# InterfaceV1_2.net
KiCad netlist of a schematic drawn in Altium Designer
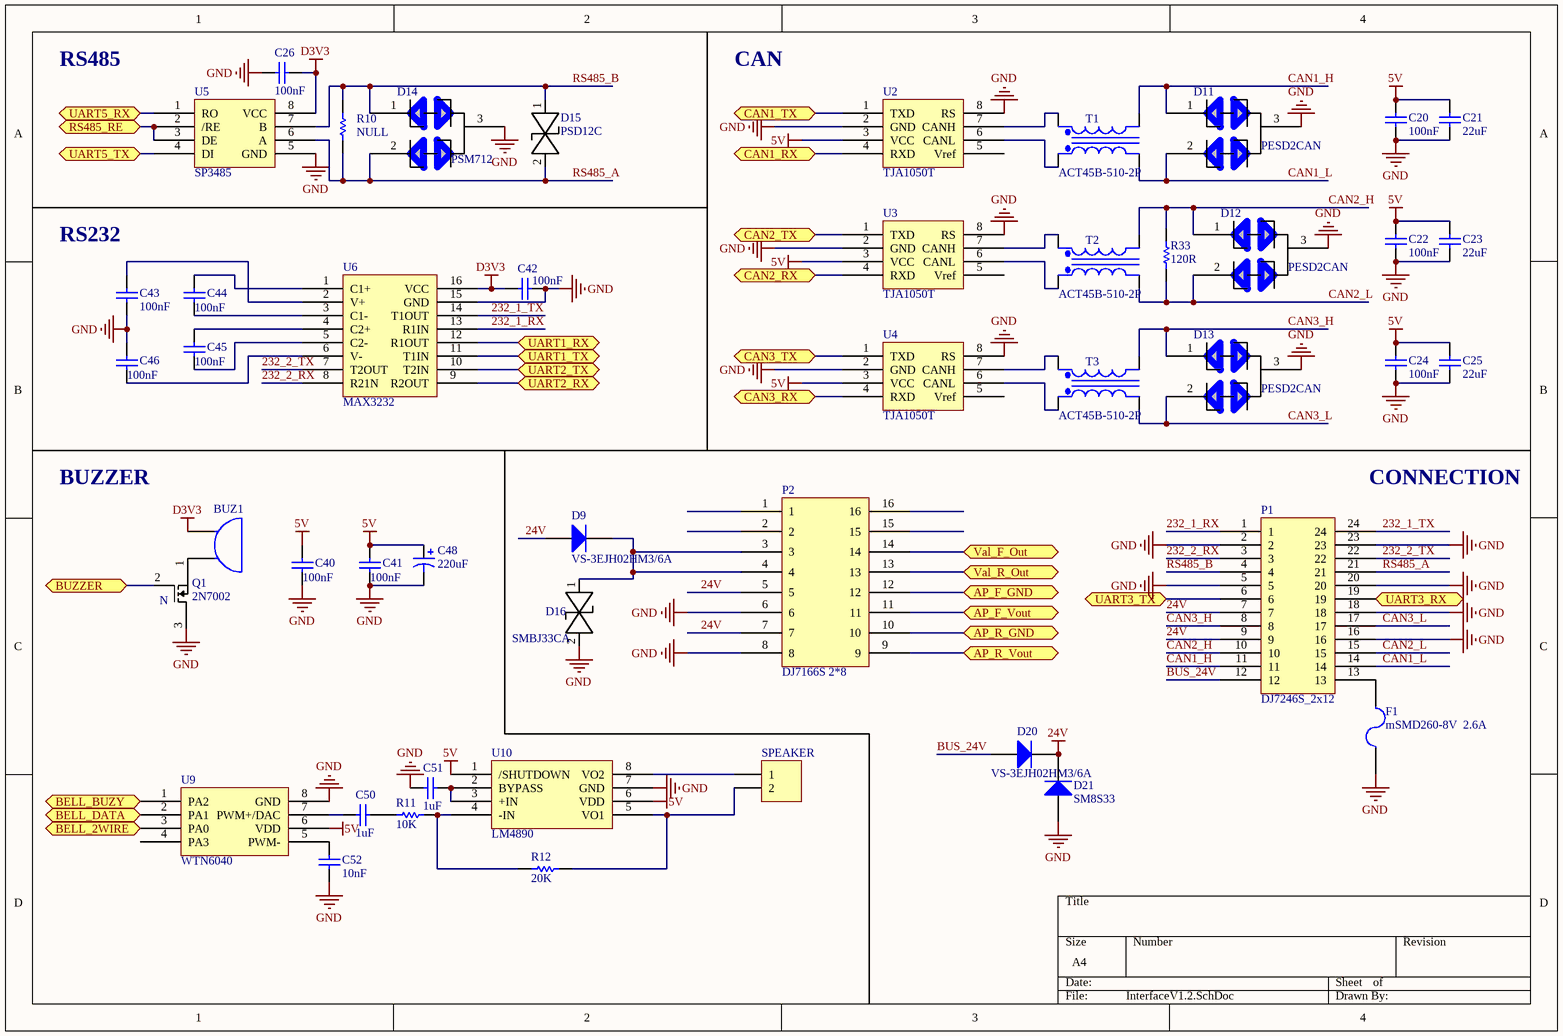
[diagram p0: InterfaceV1.2.SchDoc]

(export (version "E")
  (design (tool "Eeschema 10.0.6"))
  (components
    (comp (ref "BUZ1")
      (value "BUZZER")
      (footprint "BUZ0905")
      (description "Buzzer")
      (libsource (lib "杂元件库") (part "BUZZER"))
    )
    (comp (ref "C20")
      (value "100nF")
      (footprint "BinFeng:0402")
      (description "Capacitor")
      (fields (field (name "PUBLISHER") "Altium Limited"))
      (libsource (lib "Miscellaneous Devices") (part "Cap"))
    )
    (comp (ref "C21")
      (value "22uF")
      (footprint "0805")
      (description "Capacitor")
      (fields (field (name "PUBLISHER") "Altium Limited"))
      (libsource (lib "Miscellaneous Devices") (part "Cap"))
    )
    (comp (ref "C22")
      (value "100nF")
      (footprint "BinFeng:0402")
      (description "Capacitor")
      (fields (field (name "PUBLISHER") "Altium Limited"))
      (libsource (lib "Miscellaneous Devices") (part "Cap"))
    )
    (comp (ref "C23")
      (value "22uF")
      (footprint "0805")
      (description "Capacitor")
      (fields (field (name "PUBLISHER") "Altium Limited"))
      (libsource (lib "Miscellaneous Devices") (part "Cap"))
    )
    (comp (ref "C24")
      (value "100nF")
      (footprint "BinFeng:0402")
      (description "Capacitor")
      (fields (field (name "PUBLISHER") "Altium Limited"))
      (libsource (lib "Miscellaneous Devices") (part "Cap"))
    )
    (comp (ref "C25")
      (value "22uF")
      (footprint "0805")
      (description "Capacitor")
      (fields (field (name "PUBLISHER") "Altium Limited"))
      (libsource (lib "Miscellaneous Devices") (part "Cap"))
    )
    (comp (ref "C26")
      (value "100nF")
      (footprint "BinFeng:0603")
      (description "Capacitor")
      (fields (field (name "PUBLISHER") "Altium Limited"))
      (libsource (lib "Miscellaneous Devices") (part "Cap"))
    )
    (comp (ref "C40")
      (value "100nF")
      (footprint "BinFeng:0402")
      (description "Capacitor")
      (fields (field (name "PUBLISHER") "Altium Limited"))
      (libsource (lib "Miscellaneous Devices") (part "Cap"))
    )
    (comp (ref "C41")
      (value "100nF")
      (footprint "BinFeng:0402")
      (description "Capacitor")
      (fields (field (name "PUBLISHER") "Altium Limited"))
      (libsource (lib "Miscellaneous Devices") (part "Cap"))
    )
    (comp (ref "C42")
      (value "100nF")
      (footprint "BinFeng:0402")
      (description "Capacitor")
      (fields (field (name "PUBLISHER") "Altium Limited"))
      (libsource (lib "Miscellaneous Devices") (part "Cap"))
    )
    (comp (ref "C43")
      (value "100nF")
      (footprint "BinFeng:0402")
      (description "Capacitor")
      (fields (field (name "PUBLISHER") "Altium Limited"))
      (libsource (lib "Miscellaneous Devices") (part "Cap"))
    )
    (comp (ref "C44")
      (value "100nF")
      (footprint "BinFeng:0402")
      (description "Capacitor")
      (fields (field (name "PUBLISHER") "Altium Limited"))
      (libsource (lib "Miscellaneous Devices") (part "Cap"))
    )
    (comp (ref "C45")
      (value "100nF")
      (footprint "BinFeng:0402")
      (description "Capacitor")
      (fields (field (name "PUBLISHER") "Altium Limited"))
      (libsource (lib "Miscellaneous Devices") (part "Cap"))
    )
    (comp (ref "C46")
      (value "100nF")
      (footprint "BinFeng:0402")
      (description "Capacitor")
      (fields (field (name "PUBLISHER") "Altium Limited"))
      (libsource (lib "Miscellaneous Devices") (part "Cap"))
    )
    (comp (ref "C48")
      (value "220uF")
      (footprint "cap_pol_8*10.2")
      (description "Polarized Capacitor (Radial)")
      (fields (field (name "PUBLISHER") "Altium Limited"))
      (libsource (lib "Miscellaneous Devices") (part "Cap Pol1"))
    )
    (comp (ref "C50")
      (value "1uF")
      (footprint "BinFeng:0402")
      (description "Capacitor")
      (fields (field (name "PUBLISHER") "Altium Limited"))
      (libsource (lib "Miscellaneous Devices") (part "Cap"))
    )
    (comp (ref "C51")
      (value "1uF")
      (footprint "BinFeng:0402")
      (description "Capacitor")
      (fields (field (name "PUBLISHER") "Altium Limited"))
      (libsource (lib "Miscellaneous Devices") (part "Cap"))
    )
    (comp (ref "C52")
      (value "10nF")
      (footprint "BinFeng:0402")
      (description "Capacitor")
      (fields (field (name "PUBLISHER") "Altium Limited"))
      (libsource (lib "Miscellaneous Devices") (part "Cap"))
    )
    (comp (ref "D9")
      (value "VS-3EJH02HM3/6A")
      (footprint "hg:B290")
      (description "Default Diode")
      (fields (field (name "PUBLISHER") "Altium Limited"))
      (libsource (lib "Miscellaneous Devices") (part "Diode"))
    )
    (comp (ref "D11")
      (value "PESD2CAN")
      (footprint "SOT23")
      (libsource (lib "BinFeng_Connectors") (part "PESD1CAN"))
    )
    (comp (ref "D12")
      (value "PESD2CAN")
      (footprint "SOT23")
      (libsource (lib "BinFeng_Connectors") (part "PESD1CAN"))
    )
    (comp (ref "D13")
      (value "PESD2CAN")
      (footprint "SOT23")
      (libsource (lib "BinFeng_Connectors") (part "PESD1CAN"))
    )
    (comp (ref "D14")
      (value "PSM712")
      (footprint "SOT23")
      (libsource (lib "BinFeng_Connectors") (part "PESD1CAN"))
    )
    (comp (ref "D15") (value "PSD12C") (footprint "SOD323") (libsource (lib "BinFeng_IC") (part "PSD12C")))
    (comp (ref "D16")
      (value "SMBJ33CA")
      (footprint "hg:SMBJ33CA")
      (libsource (lib "BinFeng_IC") (part "PSD12C"))
    )
    (comp (ref "D20")
      (value "VS-3EJH02HM3/6A")
      (footprint "B290")
      (description "1 Amp General Purpose Rectifier")
      (fields (field (name "PUBLISHER") "Altium Limited"))
      (libsource (lib "Miscellaneous Devices") (part "Diode 1N4007"))
    )
    (comp (ref "D21")
      (value "SM8S33")
      (footprint "SM8S")
      (description "1 Amp General Purpose Rectifier")
      (fields (field (name "PUBLISHER") "Altium Limited"))
      (libsource (lib "Miscellaneous Devices") (part "Diode 1N4007"))
    )
    (comp (ref "F1")
      (value "mSMD260-8V  2.6A")
      (footprint "1812")
      (description "Fuse")
      (fields (field (name "PUBLISHER") "Altium Limited"))
      (libsource (lib "Miscellaneous Devices") (part "Fuse 2"))
    )
    (comp (ref "P1")
      (value "DJ7246S_2x12")
      (footprint "DJ7246S-0.7-10AW")
      (libsource (lib "hg") (part "DJ7246S-0.7-10AW"))
    )
    (comp (ref "P2")
      (value "DJ7166S 2*8")
      (footprint "hg:DJ7161S_0.7_10AW")
      (libsource (lib "hg") (part "DJ7166S"))
    )
    (comp (ref "Q1") (value "2N7002") (footprint "2N7002") (libsource (lib "seeder") (part "N-MOSFET")))
    (comp (ref "R10")
      (value "NULL")
      (footprint "BinFeng:0603")
      (description "Resistor")
      (fields (field (name "PUBLISHER") "Altium Limited"))
      (libsource (lib "Miscellaneous Devices") (part "Res1"))
    )
    (comp (ref "R11")
      (value "10K")
      (footprint "BinFeng:0402")
      (description "Resistor")
      (fields (field (name "PUBLISHER") "Altium Limited"))
      (libsource (lib "Miscellaneous Devices") (part "Res1"))
    )
    (comp (ref "R12")
      (value "20K")
      (footprint "BinFeng:0402")
      (description "Resistor")
      (fields (field (name "PUBLISHER") "Altium Limited"))
      (libsource (lib "Miscellaneous Devices") (part "Res1"))
    )
    (comp (ref "R33")
      (value "120R")
      (footprint "hg:0603")
      (description "Resistor")
      (fields (field (name "PUBLISHER") "Altium Limited"))
      (libsource (lib "Miscellaneous Devices") (part "Res1"))
    )
    (comp (ref "SPEAKER")
      (value "XH2.54-2PIN")
      (footprint "HDR1X2")
      (description "Header, 2-Pin")
      (fields (field (name "PUBLISHER") "Altium Limited"))
      (libsource (lib "Miscellaneous Connectors") (part "Header 2"))
    )
    (comp (ref "T1")
      (value "ACT45B-510-2P")
      (footprint "ACT45B-510-2P")
      (description "Transformer (Equivalent Circuit Model)")
      (fields (field (name "PUBLISHER") "Altium Limited"))
      (libsource (lib "Miscellaneous Devices") (part "Trans Eq"))
    )
    (comp (ref "T2")
      (value "ACT45B-510-2P")
      (footprint "ACT45B-510-2P")
      (description "Transformer (Equivalent Circuit Model)")
      (fields (field (name "PUBLISHER") "Altium Limited"))
      (libsource (lib "Miscellaneous Devices") (part "Trans Eq"))
    )
    (comp (ref "T3")
      (value "ACT45B-510-2P")
      (footprint "ACT45B-510-2P")
      (description "Transformer (Equivalent Circuit Model)")
      (fields (field (name "PUBLISHER") "Altium Limited"))
      (libsource (lib "Miscellaneous Devices") (part "Trans Eq"))
    )
    (comp (ref "U2")
      (value "TJA1050T")
      (footprint "SO8")
      (description "CAN Tranceiver")
      (libsource (lib "BinFeng_IC") (part "TJA1050T"))
    )
    (comp (ref "U3")
      (value "TJA1050T")
      (footprint "SO8")
      (description "CAN Tranceiver")
      (libsource (lib "BinFeng_IC") (part "TJA1050T"))
    )
    (comp (ref "U4")
      (value "TJA1050T")
      (footprint "SO8")
      (description "CAN Tranceiver")
      (libsource (lib "BinFeng_IC") (part "TJA1050T"))
    )
    (comp (ref "U5") (value "SP3485") (footprint "SO-8N") (libsource (lib "BinFeng_IC") (part "SP3485")))
    (comp (ref "U6") (value "MAX3232") (footprint "SO16") (libsource (lib "MAX3232") (part "MAX3232")))
    (comp (ref "U9") (value "WTN6040") (footprint "SO8") (libsource (lib "Schlib3") (part "WTN6040")))
    (comp (ref "U10") (value "LM4890") (footprint "MSOP8") (libsource (lib "BinFeng_IC") (part "LM4890")))
  )
  (nets
    (net (code "1") (name "/232_1_RX") (class "Default")
      (node (ref "P1") (pin "1") (pinfunction "1_1") (pintype "passive"))
      (node (ref "U6") (pin "13") (pinfunction "R1IN_13") (pintype "passive"))
    )
    (net (code "2") (name "/232_1_TX") (class "Default")
      (node (ref "P1") (pin "24") (pinfunction "24_24") (pintype "passive"))
      (node (ref "U6") (pin "14") (pinfunction "T1OUT_14") (pintype "passive"))
    )
    (net (code "3") (name "/232_2_RX") (class "Default")
      (node (ref "P1") (pin "3") (pinfunction "3_3") (pintype "passive"))
      (node (ref "U6") (pin "8") (pinfunction "R21N_8") (pintype "passive"))
    )
    (net (code "4") (name "/232_2_TX") (class "Default")
      (node (ref "P1") (pin "22") (pinfunction "22_22") (pintype "passive"))
      (node (ref "U6") (pin "7") (pinfunction "T2OUT_7") (pintype "passive"))
    )
    (net (code "5") (name "/AP_F_GND") (class "Default")
      (node (ref "P2") (pin "12") (pinfunction "12_12") (pintype "passive"))
    )
    (net (code "6") (name "/AP_F_Vout") (class "Default")
      (node (ref "P2") (pin "11") (pinfunction "11_11") (pintype "passive"))
    )
    (net (code "7") (name "/AP_R_GND") (class "Default")
      (node (ref "P2") (pin "10") (pinfunction "10_10") (pintype "passive"))
    )
    (net (code "8") (name "/AP_R_Vout") (class "Default")
      (node (ref "P2") (pin "9") (pinfunction "9_9") (pintype "passive"))
    )
    (net (code "9") (name "/BELL_2WIRE") (class "Default")
      (node (ref "U9") (pin "3") (pinfunction "PA0_3") (pintype "passive"))
    )
    (net (code "10") (name "/BELL_BUZY") (class "Default")
      (node (ref "U9") (pin "1") (pinfunction "PA2_1") (pintype "passive"))
    )
    (net (code "11") (name "/BELL_DATA") (class "Default")
      (node (ref "U9") (pin "2") (pinfunction "PA1_2") (pintype "passive"))
    )
    (net (code "12") (name "/BUS_24V") (class "Default")
      (node (ref "D20") (pin "1") (pinfunction "A_1") (pintype "passive"))
      (node (ref "P1") (pin "12") (pinfunction "12_12") (pintype "passive"))
    )
    (net (code "13") (name "/BUZZER") (class "Default")
      (node (ref "Q1") (pin "2") (pinfunction "G_2") (pintype "passive"))
    )
    (net (code "14") (name "/CAN1_H") (class "Default")
      (node (ref "D11") (pin "1") (pinfunction "11_1") (pintype "passive"))
      (node (ref "P1") (pin "11") (pinfunction "11_11") (pintype "passive"))
      (node (ref "T1") (pin "4") (pinfunction "Sec-_4") (pintype "passive"))
    )
    (net (code "15") (name "/CAN1_L") (class "Default")
      (node (ref "D11") (pin "2") (pinfunction "12_2") (pintype "passive"))
      (node (ref "P1") (pin "14") (pinfunction "14_14") (pintype "passive"))
      (node (ref "T1") (pin "2") (pinfunction "Pri-_2") (pintype "passive"))
    )
    (net (code "16") (name "/CAN1_RX") (class "Default")
      (node (ref "U2") (pin "4") (pinfunction "RXD_4") (pintype "passive"))
    )
    (net (code "17") (name "/CAN1_TX") (class "Default")
      (node (ref "U2") (pin "1") (pinfunction "TXD_1") (pintype "passive"))
    )
    (net (code "18") (name "/CAN2_H") (class "Default")
      (node (ref "D12") (pin "1") (pinfunction "11_1") (pintype "passive"))
      (node (ref "P1") (pin "10") (pinfunction "10_10") (pintype "passive"))
      (node (ref "R33") (pin "2") (pinfunction "2_2") (pintype "passive"))
      (node (ref "T2") (pin "4") (pinfunction "Sec-_4") (pintype "passive"))
    )
    (net (code "19") (name "/CAN2_L") (class "Default")
      (node (ref "D12") (pin "2") (pinfunction "12_2") (pintype "passive"))
      (node (ref "P1") (pin "15") (pinfunction "15_15") (pintype "passive"))
      (node (ref "R33") (pin "1") (pinfunction "1_1") (pintype "passive"))
      (node (ref "T2") (pin "2") (pinfunction "Pri-_2") (pintype "passive"))
    )
    (net (code "20") (name "/CAN2_RX") (class "Default")
      (node (ref "U3") (pin "4") (pinfunction "RXD_4") (pintype "passive"))
    )
    (net (code "21") (name "/CAN2_TX") (class "Default")
      (node (ref "U3") (pin "1") (pinfunction "TXD_1") (pintype "passive"))
    )
    (net (code "22") (name "/CAN3_H") (class "Default")
      (node (ref "D13") (pin "1") (pinfunction "11_1") (pintype "passive"))
      (node (ref "P1") (pin "8") (pinfunction "8_8") (pintype "passive"))
      (node (ref "T3") (pin "4") (pinfunction "Sec-_4") (pintype "passive"))
    )
    (net (code "23") (name "/CAN3_L") (class "Default")
      (node (ref "D13") (pin "2") (pinfunction "12_2") (pintype "passive"))
      (node (ref "P1") (pin "17") (pinfunction "17_17") (pintype "passive"))
      (node (ref "T3") (pin "2") (pinfunction "Pri-_2") (pintype "passive"))
    )
    (net (code "24") (name "/CAN3_RX") (class "Default")
      (node (ref "U4") (pin "4") (pinfunction "RXD_4") (pintype "passive"))
    )
    (net (code "25") (name "/CAN3_TX") (class "Default")
      (node (ref "U4") (pin "1") (pinfunction "TXD_1") (pintype "passive"))
    )
    (net (code "26") (name "/RS485_A") (class "Default")
      (node (ref "D14") (pin "2") (pinfunction "12_2") (pintype "passive"))
      (node (ref "D15") (pin "2") (pinfunction "2_2") (pintype "passive"))
      (node (ref "P1") (pin "21") (pinfunction "21_21") (pintype "passive"))
      (node (ref "R10") (pin "2") (pinfunction "2_2") (pintype "passive"))
      (node (ref "U5") (pin "6") (pinfunction "A_6") (pintype "passive"))
    )
    (net (code "27") (name "/RS485_B") (class "Default")
      (node (ref "D14") (pin "1") (pinfunction "11_1") (pintype "passive"))
      (node (ref "D15") (pin "1") (pinfunction "1_1") (pintype "passive"))
      (node (ref "P1") (pin "4") (pinfunction "4_4") (pintype "passive"))
      (node (ref "R10") (pin "1") (pinfunction "1_1") (pintype "passive"))
      (node (ref "U5") (pin "7") (pinfunction "B_7") (pintype "passive"))
    )
    (net (code "28") (name "/RS485_RE") (class "Default")
      (node (ref "U5") (pin "2") (pinfunction "/RE_2") (pintype "passive"))
      (node (ref "U5") (pin "3") (pinfunction "DE_3") (pintype "passive"))
    )
    (net (code "29") (name "/UART1_RX") (class "Default")
      (node (ref "U6") (pin "12") (pinfunction "R1OUT_12") (pintype "passive"))
    )
    (net (code "30") (name "/UART1_TX") (class "Default")
      (node (ref "U6") (pin "11") (pinfunction "T1IN_11") (pintype "passive"))
    )
    (net (code "31") (name "/UART2_RX") (class "Default")
      (node (ref "U6") (pin "9") (pinfunction "R2OUT_9") (pintype "passive"))
    )
    (net (code "32") (name "/UART2_TX") (class "Default")
      (node (ref "U6") (pin "10") (pinfunction "T2IN_10") (pintype "passive"))
    )
    (net (code "33") (name "/UART3_RX") (class "Default")
      (node (ref "P1") (pin "19") (pinfunction "19_19") (pintype "passive"))
    )
    (net (code "34") (name "/UART3_TX") (class "Default")
      (node (ref "P1") (pin "6") (pinfunction "6_6") (pintype "passive"))
    )
    (net (code "35") (name "/UART5_RX") (class "Default")
      (node (ref "U5") (pin "1") (pinfunction "RO_1") (pintype "passive"))
    )
    (net (code "36") (name "/UART5_TX") (class "Default")
      (node (ref "U5") (pin "4") (pinfunction "DI_4") (pintype "passive"))
    )
    (net (code "37") (name "/Val_F_Out") (class "Default")
      (node (ref "P2") (pin "14") (pinfunction "14_14") (pintype "passive"))
    )
    (net (code "38") (name "/Val_R_Out") (class "Default")
      (node (ref "P2") (pin "13") (pinfunction "13_13") (pintype "passive"))
    )
    (net (code "39") (name "5V") (class "Default")
      (node (ref "C20") (pin "2") (pinfunction "2_2") (pintype "passive"))
      (node (ref "C21") (pin "2") (pinfunction "2_2") (pintype "passive"))
      (node (ref "C22") (pin "2") (pinfunction "2_2") (pintype "passive"))
      (node (ref "C23") (pin "2") (pinfunction "2_2") (pintype "passive"))
      (node (ref "C24") (pin "2") (pinfunction "2_2") (pintype "passive"))
      (node (ref "C25") (pin "2") (pinfunction "2_2") (pintype "passive"))
      (node (ref "C40") (pin "2") (pinfunction "2_2") (pintype "passive"))
      (node (ref "C41") (pin "2") (pinfunction "2_2") (pintype "passive"))
      (node (ref "C48") (pin "1") (pinfunction "1_1") (pintype "passive"))
      (node (ref "U10") (pin "1") (pinfunction "/SHUTDOWN_1") (pintype "passive"))
      (node (ref "U10") (pin "6") (pinfunction "VDD_6") (pintype "passive"))
      (node (ref "U2") (pin "3") (pinfunction "VCC_3") (pintype "passive"))
      (node (ref "U3") (pin "3") (pinfunction "VCC_3") (pintype "passive"))
      (node (ref "U4") (pin "3") (pinfunction "VCC_3") (pintype "passive"))
      (node (ref "U9") (pin "6") (pinfunction "VDD_6") (pintype "power_in"))
    )
    (net (code "40") (name "24V") (class "Default")
      (node (ref "D20") (pin "2") (pinfunction "K_2") (pintype "passive"))
      (node (ref "D21") (pin "2") (pinfunction "K_2") (pintype "passive"))
      (node (ref "D9") (pin "1") (pinfunction "A_1") (pintype "passive"))
      (node (ref "P1") (pin "7") (pinfunction "7_7") (pintype "passive"))
      (node (ref "P1") (pin "9") (pinfunction "9_9") (pintype "passive"))
      (node (ref "P2") (pin "5") (pinfunction "5_5") (pintype "passive"))
      (node (ref "P2") (pin "7") (pinfunction "7_7") (pintype "passive"))
    )
    (net (code "41") (name "D3V3") (class "Default")
      (node (ref "BUZ1") (pin "1") (pinfunction "A_1") (pintype "passive"))
      (node (ref "C26") (pin "2") (pinfunction "2_2") (pintype "passive"))
      (node (ref "C42") (pin "2") (pinfunction "2_2") (pintype "passive"))
      (node (ref "U5") (pin "8") (pinfunction "VCC_8") (pintype "passive"))
      (node (ref "U6") (pin "16") (pinfunction "VCC_16") (pintype "passive"))
    )
    (net (code "42") (name "GND") (class "Default")
      (node (ref "C20") (pin "1") (pinfunction "1_1") (pintype "passive"))
      (node (ref "C21") (pin "1") (pinfunction "1_1") (pintype "passive"))
      (node (ref "C22") (pin "1") (pinfunction "1_1") (pintype "passive"))
      (node (ref "C23") (pin "1") (pinfunction "1_1") (pintype "passive"))
      (node (ref "C24") (pin "1") (pinfunction "1_1") (pintype "passive"))
      (node (ref "C25") (pin "1") (pinfunction "1_1") (pintype "passive"))
      (node (ref "C26") (pin "1") (pinfunction "1_1") (pintype "passive"))
      (node (ref "C40") (pin "1") (pinfunction "1_1") (pintype "passive"))
      (node (ref "C41") (pin "1") (pinfunction "1_1") (pintype "passive"))
      (node (ref "C42") (pin "1") (pinfunction "1_1") (pintype "passive"))
      (node (ref "C43") (pin "2") (pinfunction "2_2") (pintype "passive"))
      (node (ref "C46") (pin "2") (pinfunction "2_2") (pintype "passive"))
      (node (ref "C48") (pin "2") (pinfunction "2_2") (pintype "passive"))
      (node (ref "C51") (pin "2") (pinfunction "2_2") (pintype "passive"))
      (node (ref "C52") (pin "2") (pinfunction "2_2") (pintype "passive"))
      (node (ref "D11") (pin "3") (pinfunction "13_3") (pintype "passive"))
      (node (ref "D12") (pin "3") (pinfunction "13_3") (pintype "passive"))
      (node (ref "D13") (pin "3") (pinfunction "13_3") (pintype "passive"))
      (node (ref "D14") (pin "3") (pinfunction "13_3") (pintype "passive"))
      (node (ref "D16") (pin "2") (pinfunction "2_2") (pintype "passive"))
      (node (ref "D21") (pin "1") (pinfunction "A_1") (pintype "passive"))
      (node (ref "F1") (pin "2") (pinfunction "2_2") (pintype "passive"))
      (node (ref "P1") (pin "16") (pinfunction "16_16") (pintype "passive"))
      (node (ref "P1") (pin "18") (pinfunction "18_18") (pintype "passive"))
      (node (ref "P1") (pin "2") (pinfunction "2_2") (pintype "passive"))
      (node (ref "P1") (pin "20") (pinfunction "20_20") (pintype "passive"))
      (node (ref "P1") (pin "23") (pinfunction "23_23") (pintype "passive"))
      (node (ref "P1") (pin "5") (pinfunction "5_5") (pintype "passive"))
      (node (ref "P2") (pin "6") (pinfunction "6_6") (pintype "passive"))
      (node (ref "P2") (pin "8") (pinfunction "8_8") (pintype "passive"))
      (node (ref "Q1") (pin "3") (pinfunction "S_3") (pintype "passive"))
      (node (ref "U10") (pin "7") (pinfunction "GND_7") (pintype "passive"))
      (node (ref "U2") (pin "2") (pinfunction "GND_2") (pintype "passive"))
      (node (ref "U2") (pin "8") (pinfunction "RS_8") (pintype "passive"))
      (node (ref "U3") (pin "2") (pinfunction "GND_2") (pintype "passive"))
      (node (ref "U3") (pin "8") (pinfunction "RS_8") (pintype "passive"))
      (node (ref "U4") (pin "2") (pinfunction "GND_2") (pintype "passive"))
      (node (ref "U4") (pin "8") (pinfunction "RS_8") (pintype "passive"))
      (node (ref "U5") (pin "5") (pinfunction "GND_5") (pintype "passive"))
      (node (ref "U6") (pin "15") (pinfunction "GND_15") (pintype "passive"))
      (node (ref "U9") (pin "8") (pinfunction "GND_8") (pintype "power_in"))
    )
    (net (code "43") (name "Net-(BUZ1-B)") (class "Default")
      (node (ref "BUZ1") (pin "2") (pinfunction "B_2") (pintype "passive"))
      (node (ref "Q1") (pin "1") (pinfunction "D_1") (pintype "passive"))
    )
    (net (code "44") (name "Net-(C50-Pad1)") (class "Default")
      (node (ref "C50") (pin "1") (pinfunction "1_1") (pintype "passive"))
      (node (ref "R11") (pin "1") (pinfunction "1_1") (pintype "passive"))
    )
    (net (code "45") (name "Net-(D9-K)") (class "Default")
      (node (ref "D16") (pin "1") (pinfunction "1_1") (pintype "passive"))
      (node (ref "D9") (pin "2") (pinfunction "K_2") (pintype "passive"))
      (node (ref "P2") (pin "3") (pinfunction "3_3") (pintype "passive"))
      (node (ref "P2") (pin "4") (pinfunction "4_4") (pintype "passive"))
    )
    (net (code "46") (name "Net-(F1-Pad1)") (class "Default")
      (node (ref "F1") (pin "1") (pinfunction "1_1") (pintype "passive"))
      (node (ref "P1") (pin "13") (pinfunction "13_13") (pintype "passive"))
    )
    (net (code "47") (name "Net-(T1-Pri+)") (class "Default")
      (node (ref "T1") (pin "1") (pinfunction "Pri+_1") (pintype "passive"))
      (node (ref "U2") (pin "6") (pinfunction "CANL_6") (pintype "passive"))
    )
    (net (code "48") (name "Net-(T1-Sec+)") (class "Default")
      (node (ref "T1") (pin "3") (pinfunction "Sec+_3") (pintype "passive"))
      (node (ref "U2") (pin "7") (pinfunction "CANH_7") (pintype "passive"))
    )
    (net (code "49") (name "Net-(T2-Pri+)") (class "Default")
      (node (ref "T2") (pin "1") (pinfunction "Pri+_1") (pintype "passive"))
      (node (ref "U3") (pin "6") (pinfunction "CANL_6") (pintype "passive"))
    )
    (net (code "50") (name "Net-(T2-Sec+)") (class "Default")
      (node (ref "T2") (pin "3") (pinfunction "Sec+_3") (pintype "passive"))
      (node (ref "U3") (pin "7") (pinfunction "CANH_7") (pintype "passive"))
    )
    (net (code "51") (name "Net-(T3-Pri+)") (class "Default")
      (node (ref "T3") (pin "1") (pinfunction "Pri+_1") (pintype "passive"))
      (node (ref "U4") (pin "6") (pinfunction "CANL_6") (pintype "passive"))
    )
    (net (code "52") (name "Net-(T3-Sec+)") (class "Default")
      (node (ref "T3") (pin "3") (pinfunction "Sec+_3") (pintype "passive"))
      (node (ref "U4") (pin "7") (pinfunction "CANH_7") (pintype "passive"))
    )
    (net (code "53") (name "Net-(U6-C1+)") (class "Default")
      (node (ref "C44") (pin "2") (pinfunction "2_2") (pintype "passive"))
      (node (ref "U6") (pin "1") (pinfunction "C1+_1") (pintype "passive"))
    )
    (net (code "54") (name "Net-(U6-C1-)") (class "Default")
      (node (ref "C44") (pin "1") (pinfunction "1_1") (pintype "passive"))
      (node (ref "U6") (pin "3") (pinfunction "C1-_3") (pintype "passive"))
    )
    (net (code "55") (name "Net-(U6-C2+)") (class "Default")
      (node (ref "C45") (pin "2") (pinfunction "2_2") (pintype "passive"))
      (node (ref "U6") (pin "4") (pinfunction "C2+_4") (pintype "passive"))
    )
    (net (code "56") (name "Net-(U6-C2-)") (class "Default")
      (node (ref "C45") (pin "1") (pinfunction "1_1") (pintype "passive"))
      (node (ref "U6") (pin "5") (pinfunction "C2-_5") (pintype "passive"))
    )
    (net (code "57") (name "Net-(U6-V+)") (class "Default")
      (node (ref "C43") (pin "1") (pinfunction "1_1") (pintype "passive"))
      (node (ref "U6") (pin "2") (pinfunction "V+_2") (pintype "passive"))
    )
    (net (code "58") (name "Net-(U6-V-)") (class "Default")
      (node (ref "C46") (pin "1") (pinfunction "1_1") (pintype "passive"))
      (node (ref "U6") (pin "6") (pinfunction "V-_6") (pintype "passive"))
    )
    (net (code "59") (name "Net-(U9-PWM+{slash}DAC)") (class "Default")
      (node (ref "C50") (pin "2") (pinfunction "2_2") (pintype "passive"))
      (node (ref "U9") (pin "7") (pinfunction "PWM+/DAC_7") (pintype "passive"))
    )
    (net (code "60") (name "Net-(U9-PWM-)") (class "Default")
      (node (ref "C52") (pin "1") (pinfunction "1_1") (pintype "passive"))
      (node (ref "U9") (pin "5") (pinfunction "PWM-_5") (pintype "passive"))
    )
    (net (code "61") (name "Net-(U10-+IN)") (class "Default")
      (node (ref "C51") (pin "1") (pinfunction "1_1") (pintype "passive"))
      (node (ref "U10") (pin "2") (pinfunction "BYPASS_2") (pintype "passive"))
      (node (ref "U10") (pin "3") (pinfunction "+IN_3") (pintype "passive"))
    )
    (net (code "62") (name "Net-(U10--IN)") (class "Default")
      (node (ref "R11") (pin "2") (pinfunction "2_2") (pintype "passive"))
      (node (ref "R12") (pin "1") (pinfunction "1_1") (pintype "passive"))
      (node (ref "U10") (pin "4") (pinfunction "-IN_4") (pintype "passive"))
    )
    (net (code "63") (name "Net-(U10-VO1)") (class "Default")
      (node (ref "R12") (pin "2") (pinfunction "2_2") (pintype "passive"))
      (node (ref "SPEAKER") (pin "2") (pinfunction "2_2") (pintype "passive"))
      (node (ref "U10") (pin "5") (pinfunction "VO1_5") (pintype "passive"))
    )
    (net (code "64") (name "Net-(U10-VO2)") (class "Default")
      (node (ref "SPEAKER") (pin "1") (pinfunction "1_1") (pintype "passive"))
      (node (ref "U10") (pin "8") (pinfunction "VO2_8") (pintype "passive"))
    )
    (net (code "65") (name "unconnected-(P2-Pad1)") (class "Default")
      (node (ref "P2") (pin "1") (pinfunction "1_1") (pintype "passive"))
    )
    (net (code "66") (name "unconnected-(P2-Pad2)") (class "Default")
      (node (ref "P2") (pin "2") (pinfunction "2_2") (pintype "passive"))
    )
    (net (code "67") (name "unconnected-(P2-Pad15)") (class "Default")
      (node (ref "P2") (pin "15") (pinfunction "15_15") (pintype "passive"))
    )
    (net (code "68") (name "unconnected-(P2-Pad16)") (class "Default")
      (node (ref "P2") (pin "16") (pinfunction "16_16") (pintype "passive"))
    )
    (net (code "69") (name "unconnected-(U2-Vref-Pad5)") (class "Default")
      (node (ref "U2") (pin "5") (pinfunction "Vref_5") (pintype "passive"))
    )
    (net (code "70") (name "unconnected-(U3-Vref-Pad5)") (class "Default")
      (node (ref "U3") (pin "5") (pinfunction "Vref_5") (pintype "passive"))
    )
    (net (code "71") (name "unconnected-(U4-Vref-Pad5)") (class "Default")
      (node (ref "U4") (pin "5") (pinfunction "Vref_5") (pintype "passive"))
    )
    (net (code "72") (name "unconnected-(U9-PA3-Pad4)") (class "Default")
      (node (ref "U9") (pin "4") (pinfunction "PA3_4") (pintype "passive"))
    )
  )
)
